# ProportionalDrive.net
KiCad netlist of a schematic drawn in Altium Designer
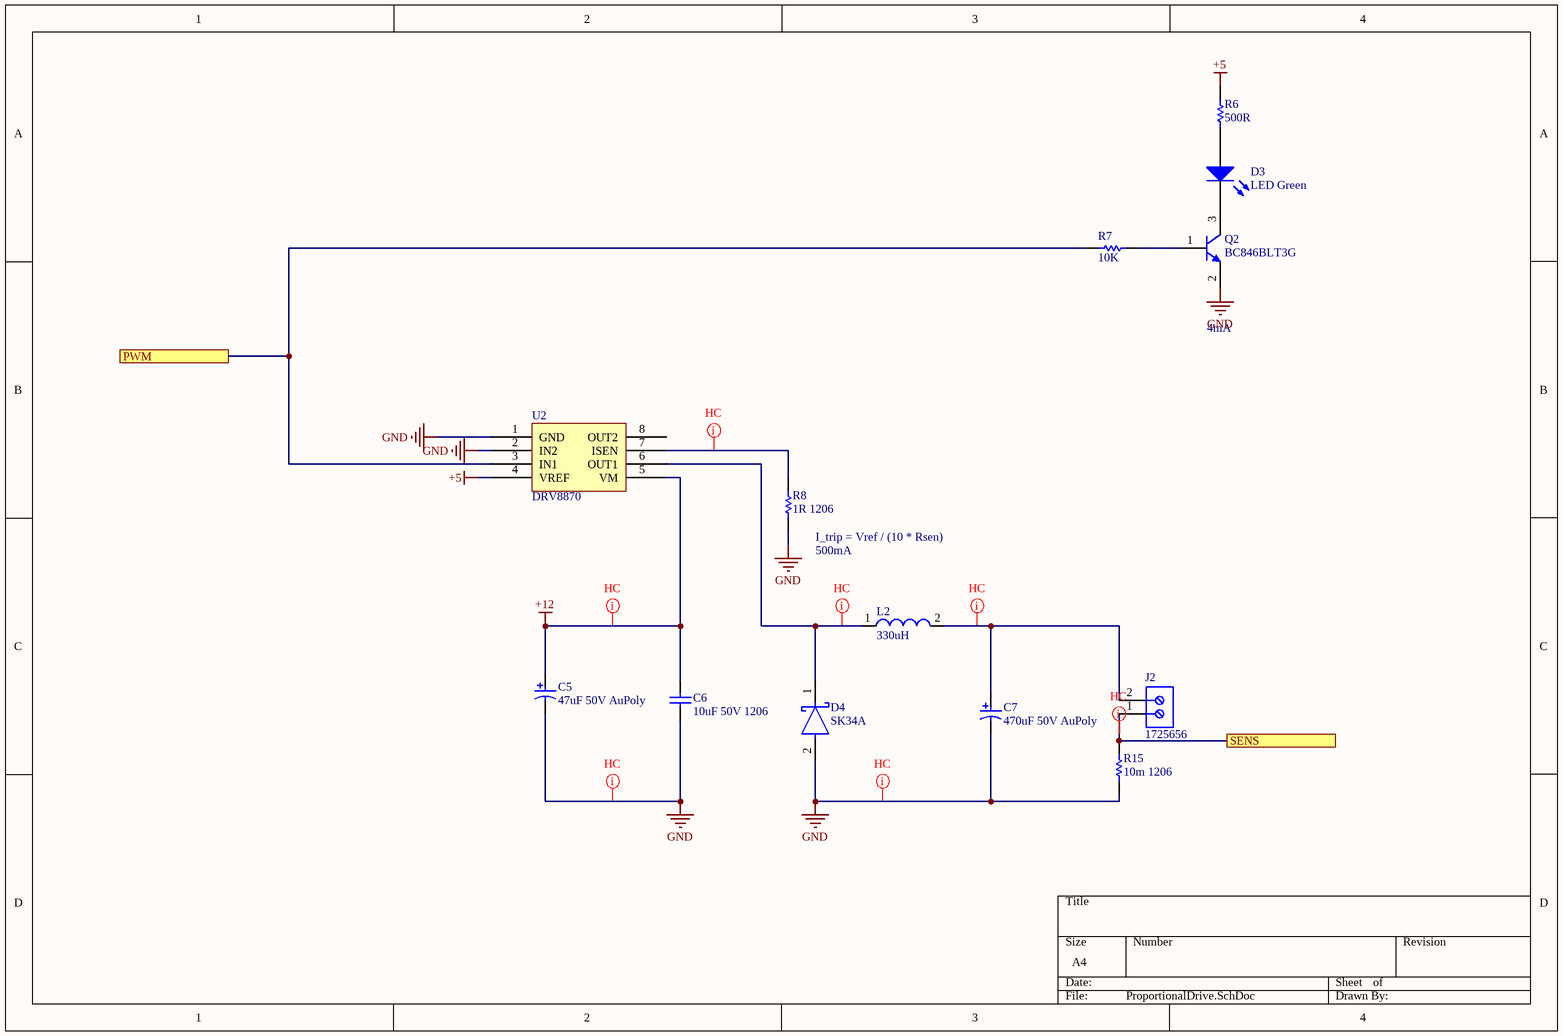
[diagram p0: ProportionalDrive.SchDoc]

(export (version "E")
  (design (tool "Eeschema 10.0.6"))
  (components
    (comp (ref "C5")
      (value "47uF 50V AuPoly")
      (footprint "EEH-ZA1H220P")
      (fields (field (name "VOLTAGE") "25VDC") (field (name "MANUFACTURER") "AVX"))
      (libsource (lib "Schlib1") (part "C-Poly"))
    )
    (comp (ref "C6")
      (value "10uF 50V 1206")
      (footprint "CAPC1206(3216)190_N")
      (description "CAP 10uF 50V ±20% 1206 (3216 Metric) Thickness 1.9mm SMD")
      (fields (field (name "TOLERANCE") "Â±20%"))
      (libsource (lib "Altium Content Vault") (part "CAP"))
    )
    (comp (ref "C7")
      (value "470uF 50V AuPoly")
      (footprint "CAPAE137130X163M")
      (fields (field (name "VOLTAGE") "25VDC") (field (name "MANUFACTURER") "AVX"))
      (libsource (lib "Schlib1") (part "C-Poly"))
    )
    (comp (ref "D3")
      (value "LED Green")
      (footprint "0603_A")
      (description "SMD mono-color Chip LED, WL-SMCW, Green")
      (fields (field (name "PARTNUMBER") "150060GS75000") (field (name "MANUFACTURER") "Wuerth Elektronik"))
      (libsource (lib "Altium Content Vault") (part "WE-LED_K1A2-2"))
    )
    (comp (ref "D4")
      (value "SK34A")
      (footprint "FP-DO-214AC-MFG")
      (description "DIODE SCHOTTKY 5A 30V SMA")
      (libsource (lib "Altium Content Vault") (part "1d6ec82d83fb6aee721767c19dac4b9"))
    )
    (comp (ref "J2")
      (value "1725656")
      (footprint "PHOE-1725656-2")
      (description "Male Header, Pitch 2.54 mm, 1 x 2 Position, Height 9 mm, Tail Length 3.5 mm")
      (fields (field (name "MANUFACTURER") "Phoenix Contact"))
      (libsource (lib "Altium Content Vault") (part "CN-1P-F-TB2"))
    )
    (comp (ref "L2")
      (value "330uH")
      (footprint "L1212")
      (fields (field (name "MANUFACTURER") "Wuerth Elektronik") (field (name "PARTNUMBER") "74479763215"))
      (libsource (lib "Schlib1") (part "Inductor1212"))
    )
    (comp (ref "Q2")
      (value "BC846BLT3G")
      (footprint "ONSC-SOT-23-3-318-08_V")
      (description "General Purpose Transistor, NPN Silicon, 3-Pin SOT-23, Pb-Free, Tape and Reel")
      (fields (field (name "MANUFACTURER") "On Semiconductor"))
      (libsource (lib "Altium Content Vault") (part "ONSC-NPN-B1E2C3-3"))
    )
    (comp (ref "R6")
      (value "500R")
      (footprint "RESC0603(1608)_L")
      (description "510R 0.1W 5% 0603 (1608 Metric)  SMD")
      (fields (field (name "POWER") "0.1 W") (field (name "TOLERANCE") "5 %"))
      (libsource (lib "Altium Content Vault") (part "RES"))
    )
    (comp (ref "R7")
      (value "10K")
      (footprint "RESC0603(1608)_N")
      (description "10K 0.1W 1% 0603 (1608 Metric)  SMD")
      (fields (field (name "POWER") "0.1 W") (field (name "TOLERANCE") "1 %"))
      (libsource (lib "Altium Content Vault") (part "RES"))
    )
    (comp (ref "R8")
      (value "1R 1206")
      (footprint "RESC1206(3216)_N")
      (description "1R2 0.25W 5% 1206 (3216 Metric)  SMD")
      (fields (field (name "POWER") "0.25 W") (field (name "TOLERANCE") "5 %"))
      (libsource (lib "Altium Content Vault") (part "RES"))
    )
    (comp (ref "R15")
      (value "10m 1206")
      (footprint "RESC1206(3216)_N")
      (description "1R2 0.25W 5% 1206 (3216 Metric)  SMD")
      (fields (field (name "POWER") "0.25 W") (field (name "TOLERANCE") "5 %"))
      (libsource (lib "Altium Content Vault") (part "RES"))
    )
    (comp (ref "U2")
      (value "DRV8870")
      (footprint "SOIC127P600X170_HS-9N")
      (libsource (lib "Schlib1") (part "DRV8870"))
    )
  )
  (nets
    (net (code "1") (name "+5") (class "Default")
      (node (ref "R6") (pin "2") (pinfunction "2_2") (pintype "passive"))
      (node (ref "U2") (pin "4") (pinfunction "VREF_4") (pintype "passive"))
    )
    (net (code "2") (name "+12") (class "Default")
      (node (ref "C5") (pin "1") (pinfunction "1_1") (pintype "passive"))
      (node (ref "C6") (pin "2") (pinfunction "2_2") (pintype "passive"))
      (node (ref "U2") (pin "5") (pinfunction "VM_5") (pintype "passive"))
    )
    (net (code "3") (name "/PWM") (class "Default")
      (node (ref "R7") (pin "1") (pinfunction "1_1") (pintype "passive"))
      (node (ref "U2") (pin "3") (pinfunction "IN1_3") (pintype "passive"))
    )
    (net (code "4") (name "/SENS") (class "Default")
      (node (ref "J2") (pin "1") (pinfunction "1_1") (pintype "passive"))
      (node (ref "R15") (pin "2") (pinfunction "2_2") (pintype "passive"))
    )
    (net (code "5") (name "GND") (class "Default")
      (node (ref "C5") (pin "2") (pinfunction "2_2") (pintype "passive"))
      (node (ref "C6") (pin "1") (pinfunction "1_1") (pintype "passive"))
      (node (ref "C7") (pin "2") (pinfunction "2_2") (pintype "passive"))
      (node (ref "D4") (pin "2") (pinfunction "A_2") (pintype "passive"))
      (node (ref "Q2") (pin "2") (pinfunction "E_2") (pintype "passive"))
      (node (ref "R15") (pin "1") (pinfunction "1_1") (pintype "passive"))
      (node (ref "R8") (pin "1") (pinfunction "1_1") (pintype "passive"))
      (node (ref "U2") (pin "1") (pinfunction "GND_1") (pintype "passive"))
      (node (ref "U2") (pin "2") (pinfunction "IN2_2") (pintype "passive"))
    )
    (net (code "6") (name "Net-(C7-Pad1)") (class "Default")
      (node (ref "C7") (pin "1") (pinfunction "1_1") (pintype "passive"))
      (node (ref "J2") (pin "2") (pinfunction "2_2") (pintype "passive"))
      (node (ref "L2") (pin "2") (pinfunction "2_2") (pintype "passive"))
    )
    (net (code "7") (name "Net-(D3-A)") (class "Default")
      (node (ref "D3") (pin "2") (pinfunction "A_2") (pintype "passive"))
      (node (ref "R6") (pin "1") (pinfunction "1_1") (pintype "passive"))
    )
    (net (code "8") (name "Net-(D3-K)") (class "Default")
      (node (ref "D3") (pin "1") (pinfunction "K_1") (pintype "passive"))
      (node (ref "Q2") (pin "3") (pinfunction "C_3") (pintype "passive"))
    )
    (net (code "9") (name "Net-(D4-C)") (class "Default")
      (node (ref "D4") (pin "1") (pinfunction "C_1") (pintype "passive"))
      (node (ref "L2") (pin "1") (pinfunction "1_1") (pintype "passive"))
      (node (ref "U2") (pin "6") (pinfunction "OUT1_6") (pintype "passive"))
    )
    (net (code "10") (name "Net-(Q2-B)") (class "Default")
      (node (ref "Q2") (pin "1") (pinfunction "B_1") (pintype "passive"))
      (node (ref "R7") (pin "2") (pinfunction "2_2") (pintype "passive"))
    )
    (net (code "11") (name "Net-(U2-ISEN)") (class "Default")
      (node (ref "R8") (pin "2") (pinfunction "2_2") (pintype "passive"))
      (node (ref "U2") (pin "7") (pinfunction "ISEN_7") (pintype "passive"))
    )
    (net (code "12") (name "unconnected-(U2-OUT2-Pad8)") (class "Default")
      (node (ref "U2") (pin "8") (pinfunction "OUT2_8") (pintype "passive"))
    )
  )
)
